# Usb_to_i2c.net
KiCad netlist of a schematic drawn in Altium Designer
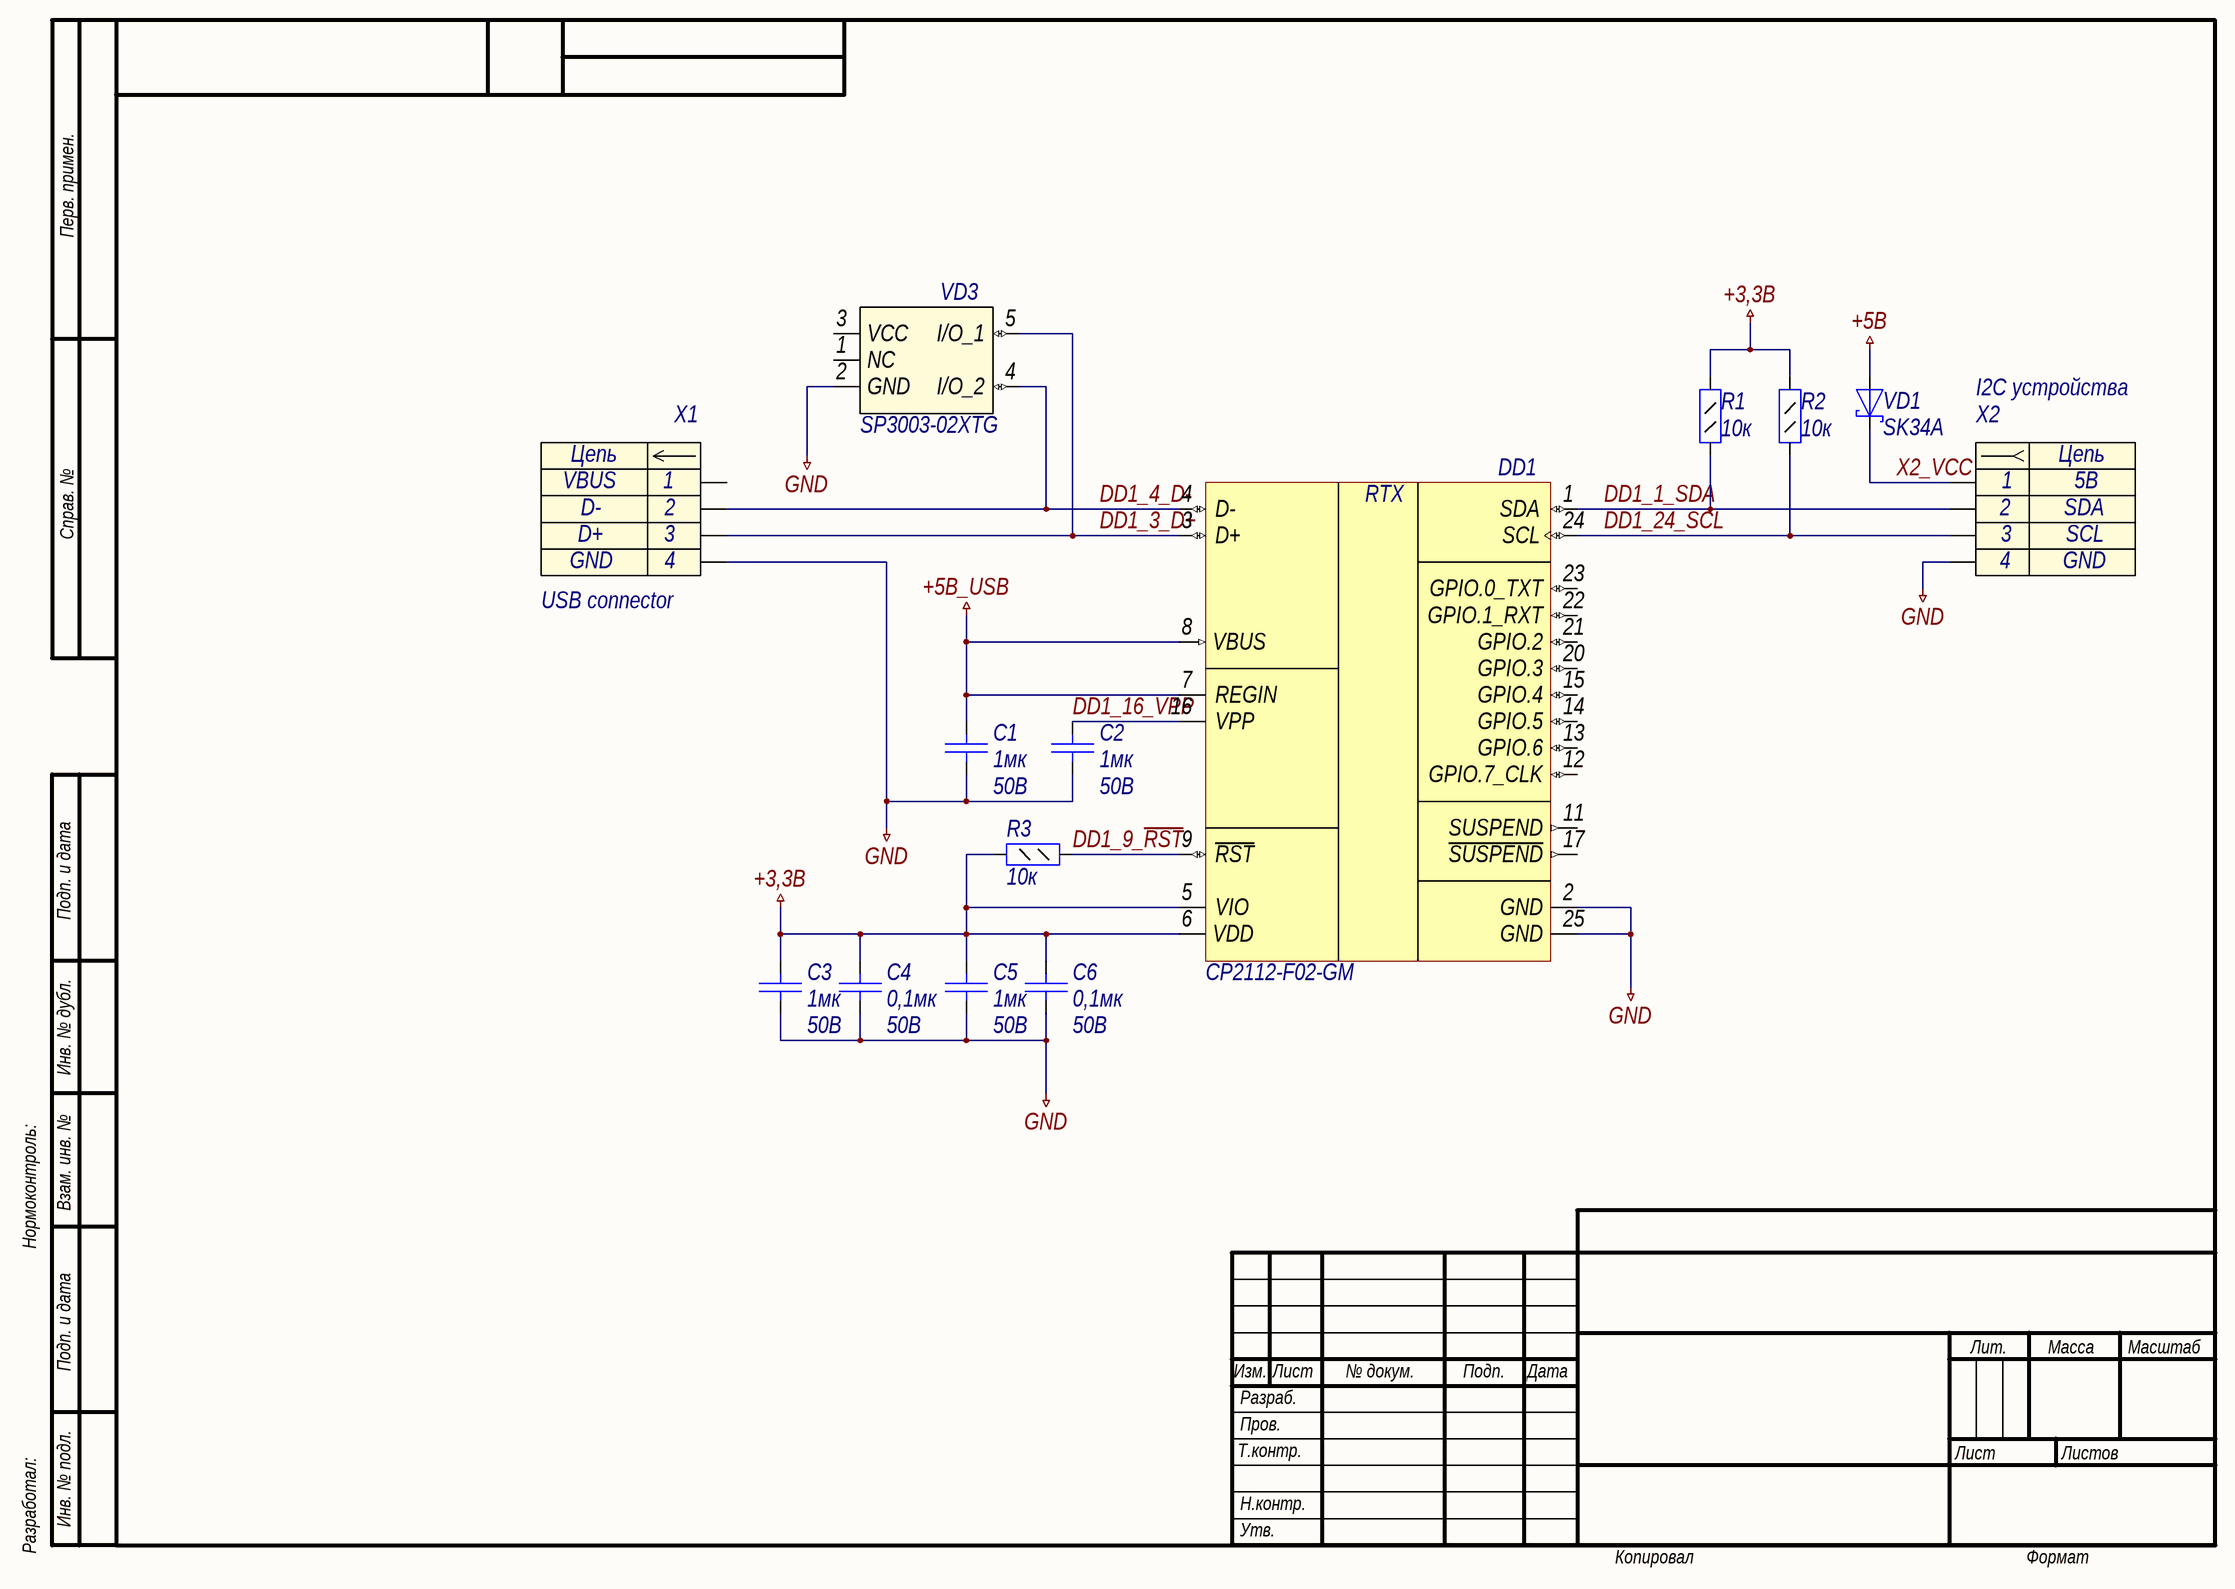
[diagram p0: Usb_to_i2c.schdoc]

(export (version "E")
  (design (tool "Eeschema 10.0.6"))
  (components
    (comp (ref "C1")
      (value "1мк")
      (footprint "C0603")
      (description "Конденсатор")
      (fields
        (field (name "VOLTAGE") "50B")
        (field (name "PART NUMBER") "GRM188R71C105KA12D**")
        (field (name "Comment") "Capacitor")
      )
      (libsource (lib "MOP44") (part "Capacitor"))
    )
    (comp (ref "C2")
      (value "1мк")
      (footprint "C0603")
      (description "Конденсатор")
      (fields
        (field (name "VOLTAGE") "50B")
        (field (name "PART NUMBER") "GRM188R71C105KA12D**")
        (field (name "Comment") "Capacitor")
      )
      (libsource (lib "MOP44") (part "Capacitor"))
    )
    (comp (ref "C3")
      (value "1мк")
      (footprint "C0603")
      (description "Конденсатор")
      (fields
        (field (name "VOLTAGE") "50B")
        (field (name "PART NUMBER") "GRM188R71C105KA12D**")
        (field (name "Comment") "Capacitor")
      )
      (libsource (lib "MOP44") (part "Capacitor"))
    )
    (comp (ref "C4")
      (value "0,1мк")
      (footprint "C0603")
      (description "Конденсатор")
      (fields
        (field (name "VOLTAGE") "50B")
        (field (name "PART NUMBER") "GRM188R71H104K")
        (field (name "Comment") "Capacitor")
      )
      (libsource (lib "MOP44") (part "Capacitor"))
    )
    (comp (ref "C5")
      (value "1мк")
      (footprint "C0603")
      (description "Конденсатор")
      (fields
        (field (name "VOLTAGE") "50B")
        (field (name "PART NUMBER") "GRM188R71C105KA12D**")
        (field (name "Comment") "Capacitor")
      )
      (libsource (lib "MOP44") (part "Capacitor"))
    )
    (comp (ref "C6")
      (value "0,1мк")
      (footprint "C0603")
      (description "Конденсатор")
      (fields
        (field (name "VOLTAGE") "50B")
        (field (name "PART NUMBER") "GRM188R71H104K")
        (field (name "Comment") "Capacitor")
      )
      (libsource (lib "MOP44") (part "Capacitor"))
    )
    (comp (ref "DD1")
      (value "CP2112-F02-GM")
      (footprint "QFN24")
      (description "USB-I2C преобразователь")
      (libsource (lib "MOP44") (part "CP2112-F02-GM"))
    )
    (comp (ref "R1")
      (value "10к")
      (footprint "R0805")
      (description "Резистор")
      (fields (field (name "PART NUMBER") "RC0805FR-0710KL") (field (name "POWER") "0,125Вт"))
      (libsource (lib "MOP44") (part "Resistor_0,125Вт"))
    )
    (comp (ref "R2")
      (value "10к")
      (footprint "R0805")
      (description "Резистор")
      (fields (field (name "PART NUMBER") "RC0805FR-0710KL") (field (name "POWER") "0,125Вт"))
      (libsource (lib "MOP44") (part "Resistor_0,125Вт"))
    )
    (comp (ref "R3")
      (value "10к")
      (footprint "R0805")
      (description "Резистор")
      (fields (field (name "PART NUMBER") "RC0805FR-0710KL") (field (name "POWER") "0,125Вт"))
      (libsource (lib "") (part "Resistor_0,125Вт_1"))
    )
    (comp (ref "VD1")
      (value "DiodeSchottky")
      (footprint "SMA")
      (description "Диод Шоттки")
      (fields (field (name "PART NUMBER") "SK34A"))
      (libsource (lib "MOP44") (part "DiodeSchottky"))
    )
    (comp (ref "VD3")
      (value "SP3003-02XTG")
      (footprint "SOT553")
      (description "Двухканальная ESD защита USB")
      (libsource (lib "MOP44") (part "SP3003-02XTG"))
    )
    (comp (ref "X1")
      (value "USB connector")
      (footprint "USB 2.0 A PLUG")
      (description "Разъем - 4 конт. вилка")
      (fields (field (name "PART NUMBER") "UP2-AH-1-TH"))
      (libsource (lib "MOP44") (part "Header_4_plg"))
    )
    (comp (ref "X2")
      (value "Header_4_sct")
      (footprint "PLS-4HOLES")
      (description "Разъем - 4 конт. розетка")
      (fields (field (name "PART NAME") "I2C устройства"))
      (libsource (lib "MOP44") (part "Header_4_sct"))
    )
  )
  (nets
    (net (code "1") (name "+3,3В") (class "Default")
      (node (ref "C3") (pin "2") (pinfunction "2_2") (pintype "passive"))
      (node (ref "C4") (pin "2") (pinfunction "2_2") (pintype "passive"))
      (node (ref "C5") (pin "2") (pinfunction "2_2") (pintype "passive"))
      (node (ref "C6") (pin "2") (pinfunction "2_2") (pintype "passive"))
      (node (ref "DD1") (pin "5") (pinfunction "VIO_5") (pintype "power_in"))
      (node (ref "DD1") (pin "6") (pinfunction "VDD_6") (pintype "power_in"))
      (node (ref "R1") (pin "2") (pinfunction "2_2") (pintype "passive"))
      (node (ref "R2") (pin "2") (pinfunction "2_2") (pintype "passive"))
      (node (ref "R3") (pin "2") (pinfunction "2_2") (pintype "passive"))
    )
    (net (code "2") (name "+5В") (class "Default")
      (node (ref "VD1") (pin "2") (pinfunction "A_2") (pintype "passive"))
    )
    (net (code "3") (name "+5В_USB") (class "Default")
      (node (ref "C1") (pin "2") (pinfunction "2_2") (pintype "passive"))
      (node (ref "DD1") (pin "7") (pinfunction "REGIN_7") (pintype "power_in"))
      (node (ref "DD1") (pin "8") (pinfunction "VBUS_8") (pintype "input"))
    )
    (net (code "4") (name "/DD1_1_SDA") (class "Default")
      (node (ref "DD1") (pin "1") (pinfunction "SDA_1") (pintype "bidirectional"))
      (node (ref "R1") (pin "1") (pinfunction "1_1") (pintype "passive"))
      (node (ref "X2") (pin "2") (pinfunction "2_2") (pintype "passive"))
    )
    (net (code "5") (name "/DD1_3_D+") (class "Default")
      (node (ref "DD1") (pin "3") (pinfunction "D+_3") (pintype "bidirectional"))
      (node (ref "VD3") (pin "5") (pinfunction "I/O_1_5") (pintype "bidirectional"))
      (node (ref "X1") (pin "3") (pinfunction "3_3") (pintype "passive"))
    )
    (net (code "6") (name "/DD1_4_D-") (class "Default")
      (node (ref "DD1") (pin "4") (pinfunction "D-_4") (pintype "bidirectional"))
      (node (ref "VD3") (pin "4") (pinfunction "I/O_2_4") (pintype "bidirectional"))
      (node (ref "X1") (pin "2") (pinfunction "2_2") (pintype "passive"))
    )
    (net (code "7") (name "/DD1_9_~{RST}") (class "Default")
      (node (ref "DD1") (pin "9") (pinfunction "~{RST}_9") (pintype "bidirectional"))
      (node (ref "R3") (pin "1") (pinfunction "1_1") (pintype "passive"))
    )
    (net (code "8") (name "/DD1_16_VPP") (class "Default")
      (node (ref "C2") (pin "2") (pinfunction "2_2") (pintype "passive"))
      (node (ref "DD1") (pin "16") (pinfunction "VPP_16") (pintype "passive"))
    )
    (net (code "9") (name "/DD1_24_SCL") (class "Default")
      (node (ref "DD1") (pin "24") (pinfunction "SCL_24") (pintype "bidirectional"))
      (node (ref "R2") (pin "1") (pinfunction "1_1") (pintype "passive"))
      (node (ref "X2") (pin "3") (pinfunction "3_3") (pintype "passive"))
    )
    (net (code "10") (name "/X2_VCC") (class "Default")
      (node (ref "VD1") (pin "1") (pinfunction "K_1") (pintype "passive"))
      (node (ref "X2") (pin "1") (pinfunction "1_1") (pintype "passive"))
    )
    (net (code "11") (name "GND") (class "Default")
      (node (ref "C1") (pin "1") (pinfunction "1_1") (pintype "passive"))
      (node (ref "C2") (pin "1") (pinfunction "1_1") (pintype "passive"))
      (node (ref "C3") (pin "1") (pinfunction "1_1") (pintype "passive"))
      (node (ref "C4") (pin "1") (pinfunction "1_1") (pintype "passive"))
      (node (ref "C5") (pin "1") (pinfunction "1_1") (pintype "passive"))
      (node (ref "C6") (pin "1") (pinfunction "1_1") (pintype "passive"))
      (node (ref "DD1") (pin "2") (pinfunction "GND_2") (pintype "power_in"))
      (node (ref "DD1") (pin "25") (pinfunction "GND_25") (pintype "power_in"))
      (node (ref "VD3") (pin "2") (pinfunction "GND_2") (pintype "passive"))
      (node (ref "X1") (pin "4") (pinfunction "4_4") (pintype "passive"))
      (node (ref "X2") (pin "4") (pinfunction "4_4") (pintype "passive"))
    )
    (net (code "12") (name "unconnected-(DD1-GPIO.0_TXT-Pad23)") (class "Default")
      (node (ref "DD1") (pin "23") (pinfunction "GPIO.0_TXT_23") (pintype "bidirectional"))
    )
    (net (code "13") (name "unconnected-(DD1-GPIO.1_RXT-Pad22)") (class "Default")
      (node (ref "DD1") (pin "22") (pinfunction "GPIO.1_RXT_22") (pintype "bidirectional"))
    )
    (net (code "14") (name "unconnected-(DD1-GPIO.2-Pad21)") (class "Default")
      (node (ref "DD1") (pin "21") (pinfunction "GPIO.2_21") (pintype "bidirectional"))
    )
    (net (code "15") (name "unconnected-(DD1-GPIO.3-Pad20)") (class "Default")
      (node (ref "DD1") (pin "20") (pinfunction "GPIO.3_20") (pintype "bidirectional"))
    )
    (net (code "16") (name "unconnected-(DD1-GPIO.4-Pad15)") (class "Default")
      (node (ref "DD1") (pin "15") (pinfunction "GPIO.4_15") (pintype "bidirectional"))
    )
    (net (code "17") (name "unconnected-(DD1-GPIO.5-Pad14)") (class "Default")
      (node (ref "DD1") (pin "14") (pinfunction "GPIO.5_14") (pintype "bidirectional"))
    )
    (net (code "18") (name "unconnected-(DD1-GPIO.6-Pad13)") (class "Default")
      (node (ref "DD1") (pin "13") (pinfunction "GPIO.6_13") (pintype "bidirectional"))
    )
    (net (code "19") (name "unconnected-(DD1-GPIO.7_CLK-Pad12)") (class "Default")
      (node (ref "DD1") (pin "12") (pinfunction "GPIO.7_CLK_12") (pintype "bidirectional"))
    )
    (net (code "20") (name "unconnected-(DD1-SUSPEND-Pad11)") (class "Default")
      (node (ref "DD1") (pin "11") (pinfunction "SUSPEND_11") (pintype "output"))
    )
    (net (code "21") (name "unconnected-(DD1-~{SUSPEND}-Pad17)") (class "Default")
      (node (ref "DD1") (pin "17") (pinfunction "~{SUSPEND}_17") (pintype "output"))
    )
    (net (code "22") (name "unconnected-(VD3-NC-Pad1)") (class "Default")
      (node (ref "VD3") (pin "1") (pinfunction "NC_1") (pintype "passive"))
    )
    (net (code "23") (name "unconnected-(VD3-VCC-Pad3)") (class "Default")
      (node (ref "VD3") (pin "3") (pinfunction "VCC_3") (pintype "power_in"))
    )
    (net (code "24") (name "unconnected-(X1-Pad1)") (class "Default")
      (node (ref "X1") (pin "1") (pinfunction "1_1") (pintype "passive"))
    )
  )
)
